# main.net
KiCad netlist of a schematic drawn in Altium Designer
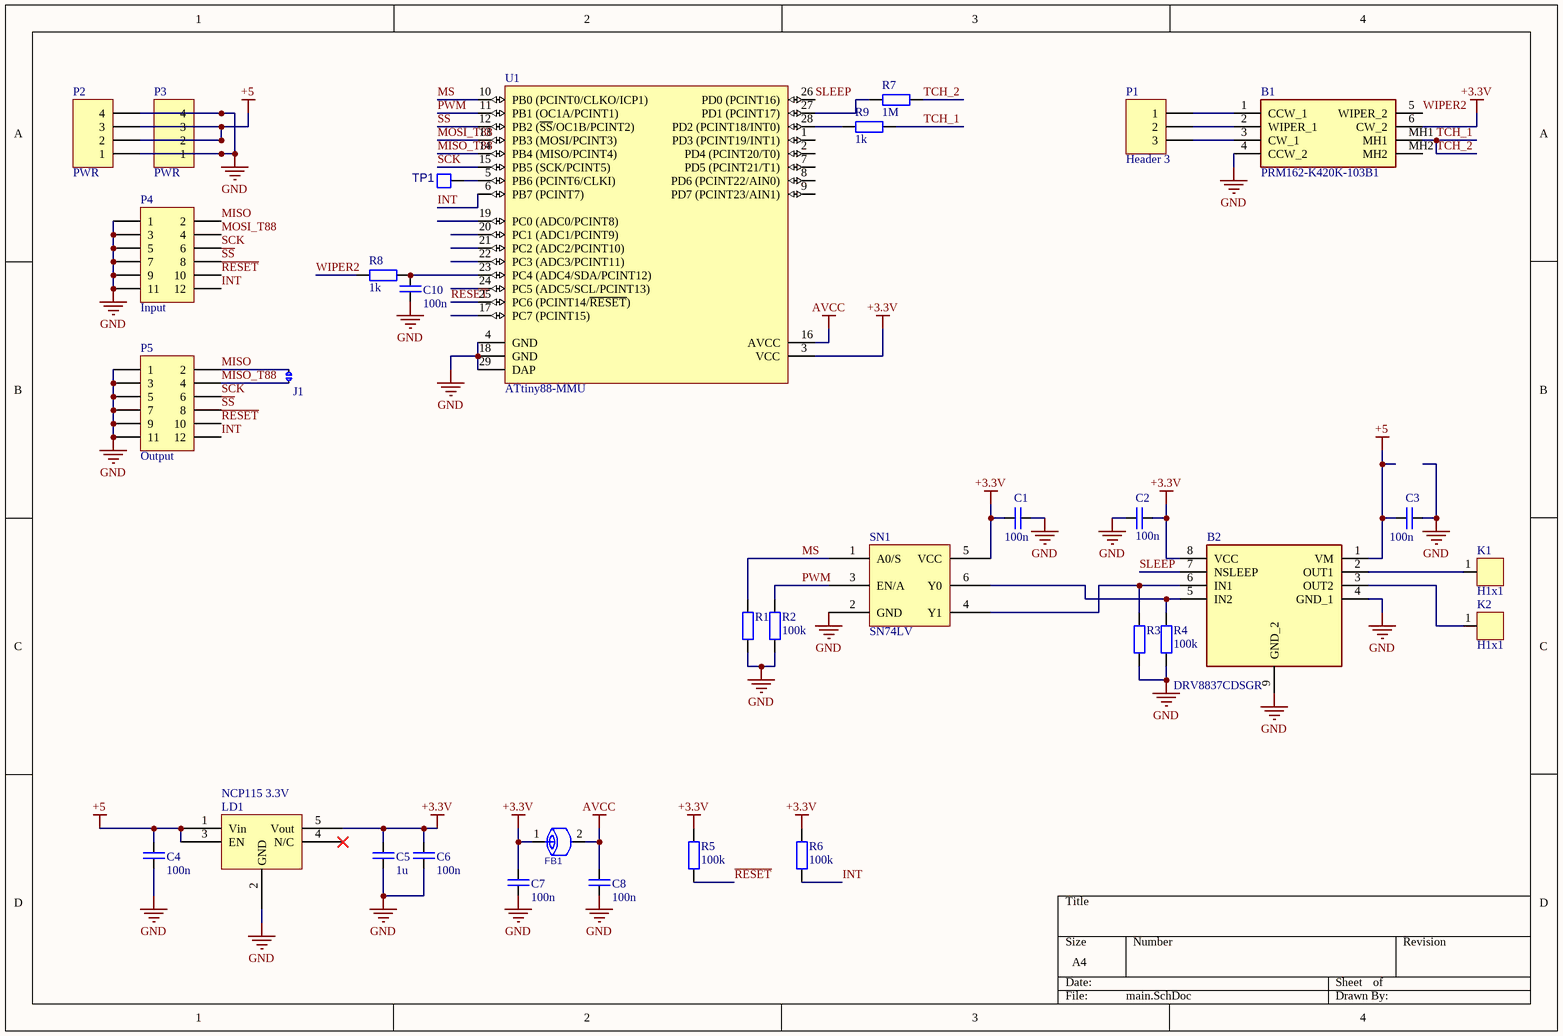
[diagram p0: main.SchDoc]

(export (version "E")
  (design (tool "Eeschema 10.0.6"))
  (components
    (comp (ref "B1")
      (value "PRM162-K420K-103B1")
      (footprint "PRM162K415K103B1")
      (description "Potentiometers 10KOHMS KNURLED DUAL NO DET")
      (fields (field (name "MOUSER PART NUMBER") "652-PRM162K420K103B1"))
      (libsource (lib "PRM162-K420K-103B1") (part "PRM162-K420K-103B1"))
    )
    (comp (ref "B2")
      (value "DRV8837CDSGR")
      (footprint "SON50P200X200X80-9N")
      (description "1A Low-Voltage H-Bridge Driver")
      (fields (field (name "MOUSER PART NUMBER") "595-DRV8837CDSGR"))
      (libsource (lib "DRV8837CDSGR") (part "DRV8837CDSGR"))
    )
    (comp (ref "C1")
      (value "100n")
      (footprint "R1005_0402i_M")
      (description "Capacitor")
      (libsource (lib "General") (part "C"))
    )
    (comp (ref "C2")
      (value "100n")
      (footprint "R1005_0402i_M")
      (description "Capacitor")
      (libsource (lib "General") (part "C"))
    )
    (comp (ref "C3")
      (value "100n")
      (footprint "R1005_0402i_M")
      (description "Capacitor")
      (libsource (lib "General") (part "C"))
    )
    (comp (ref "C4")
      (value "100n")
      (footprint "R1005_0402i_L")
      (description "Capacitor")
      (libsource (lib "General") (part "C"))
    )
    (comp (ref "C5")
      (value "1u")
      (footprint "C1608_0603I_L")
      (description "Capacitor")
      (libsource (lib "General") (part "C"))
    )
    (comp (ref "C6")
      (value "100n")
      (footprint "R1005_0402i_L")
      (description "Capacitor")
      (libsource (lib "General") (part "C"))
    )
    (comp (ref "C7")
      (value "100n")
      (footprint "R1005_0402i_L")
      (description "Capacitor")
      (libsource (lib "General") (part "C"))
    )
    (comp (ref "C8")
      (value "100n")
      (footprint "R1005_0402i_L")
      (description "Capacitor")
      (libsource (lib "General") (part "C"))
    )
    (comp (ref "C10")
      (value "100n")
      (footprint "R1005_0402i_M")
      (description "Capacitor")
      (libsource (lib "General") (part "C"))
    )
    (comp (ref "FB1")
      (value "FERITTE BEAD")
      (footprint "R1608_0603I_L")
      (libsource (lib "General") (part "FERITTE BEAD"))
    )
    (comp (ref "J1")
      (value "Terminator")
      (footprint "solderJumper")
      (libsource (lib "Kon_Tipk") (part "JMP_mini"))
    )
    (comp (ref "K1")
      (value "H1x1")
      (footprint "H1x1")
      (description "Header 1x1 (male)")
      (libsource (lib "Kon_Tipk") (part "H1x1"))
    )
    (comp (ref "K2")
      (value "H1x1")
      (footprint "H1x1")
      (description "Header 1x1 (male)")
      (libsource (lib "Kon_Tipk") (part "H1x1"))
    )
    (comp (ref "LD1")
      (value "NCP115 3.3V")
      (footprint "TSOP95P280X110-6L")
      (libsource (lib "led_ring") (part "NCP115 3.3V"))
    )
    (comp (ref "P1")
      (value "Header 3")
      (footprint "HDR1X3")
      (description "Header, 3-Pin")
      (fields (field (name "PUBLISHER") "Altium Limited"))
      (libsource (lib "Miscellaneous Connectors") (part "Header 3"))
    )
    (comp (ref "P2")
      (value "PWR")
      (footprint "HDR1X4")
      (description "Header, 4-Pin")
      (fields (field (name "PUBLISHER") "Altium Limited"))
      (libsource (lib "Miscellaneous Connectors") (part "Header 4"))
    )
    (comp (ref "P3")
      (value "PWR")
      (footprint "HDR1X4")
      (description "Header, 4-Pin")
      (fields (field (name "PUBLISHER") "Altium Limited"))
      (libsource (lib "Miscellaneous Connectors") (part "Header 4"))
    )
    (comp (ref "P4")
      (value "Input")
      (footprint "1.27mm SMD conn")
      (description "Header, 6-Pin, Dual row")
      (fields (field (name "PUBLISHER") "Altium Limited"))
      (libsource (lib "Miscellaneous Connectors") (part "Header 6X2"))
    )
    (comp (ref "P5")
      (value "Output")
      (footprint "1.27mm SMD conn")
      (description "Header, 6-Pin, Dual row")
      (fields (field (name "PUBLISHER") "Altium Limited"))
      (libsource (lib "Miscellaneous Connectors") (part "Header 6X2"))
    )
    (comp (ref "R1")
      (value "100k")
      (footprint "R1005_0402i_L")
      (description "R")
      (libsource (lib "General") (part "R"))
    )
    (comp (ref "R2")
      (value "100k")
      (footprint "R1005_0402i_L")
      (description "R")
      (libsource (lib "General") (part "R"))
    )
    (comp (ref "R3")
      (value "100k")
      (footprint "R1005_0402i_L")
      (description "R")
      (libsource (lib "General") (part "R"))
    )
    (comp (ref "R4")
      (value "100k")
      (footprint "R1005_0402i_L")
      (description "R")
      (libsource (lib "General") (part "R"))
    )
    (comp (ref "R5")
      (value "100k")
      (footprint "R1005_0402i_L")
      (description "R")
      (libsource (lib "General") (part "R"))
    )
    (comp (ref "R6")
      (value "100k")
      (footprint "R1005_0402i_L")
      (description "R")
      (libsource (lib "General") (part "R"))
    )
    (comp (ref "R7")
      (value "1M")
      (footprint "R1005_0402i_L")
      (description "R")
      (libsource (lib "General") (part "R"))
    )
    (comp (ref "R8")
      (value "1k")
      (footprint "R1005_0402i_L")
      (description "R")
      (libsource (lib "General") (part "R"))
    )
    (comp (ref "R9")
      (value "1k")
      (footprint "R1005_0402i_L")
      (description "R")
      (libsource (lib "General") (part "R"))
    )
    (comp (ref "SN1")
      (value "SN74LV")
      (footprint "SON35P100X40-6N")
      (libsource (lib "SN74LVC1G18DSFR") (part "SN74LV"))
    )
    (comp (ref "TP1") (value "PAD") (footprint "PAD") (libsource (lib "General") (part "PAD")))
    (comp (ref "U1")
      (value "ATtiny88-MMU")
      (footprint "28M1_N")
      (fields (field (name "PUBLISHER") "Altium Limited"))
      (libsource (lib "Atmel Microcontroller 8-Bit tinyAVR") (part "ATtiny88-MMU"))
    )
  )
  (nets
    (net (code "1") (name "+3.3V") (class "Default")
      (node (ref "B1") (pin "6") (pinfunction "CW_2_6") (pintype "passive"))
      (node (ref "B2") (pin "8") (pinfunction "VCC_8") (pintype "passive"))
      (node (ref "C1") (pin "2") (pinfunction "2_2") (pintype "passive"))
      (node (ref "C2") (pin "2") (pinfunction "2_2") (pintype "passive"))
      (node (ref "C5") (pin "1") (pinfunction "1_1") (pintype "passive"))
      (node (ref "C6") (pin "1") (pinfunction "1_1") (pintype "passive"))
      (node (ref "C7") (pin "1") (pinfunction "1_1") (pintype "passive"))
      (node (ref "FB1") (pin "1") (pintype "passive"))
      (node (ref "LD1") (pin "5") (pinfunction "Vout_5") (pintype "passive"))
      (node (ref "R5") (pin "1") (pintype "passive"))
      (node (ref "R6") (pin "1") (pintype "passive"))
      (node (ref "SN1") (pin "5") (pinfunction "VCC_5") (pintype "passive"))
      (node (ref "U1") (pin "3") (pinfunction "VCC_3") (pintype "power_in"))
    )
    (net (code "2") (name "+5") (class "Default")
      (node (ref "B2") (pin "1") (pinfunction "VM_1") (pintype "passive"))
      (node (ref "C3") (pin "1") (pinfunction "1_1") (pintype "passive"))
      (node (ref "C4") (pin "1") (pinfunction "1_1") (pintype "passive"))
      (node (ref "LD1") (pin "1") (pinfunction "Vin_1") (pintype "passive"))
      (node (ref "LD1") (pin "3") (pinfunction "EN_3") (pintype "passive"))
      (node (ref "P2") (pin "2") (pinfunction "2_2") (pintype "passive"))
      (node (ref "P2") (pin "3") (pinfunction "3_3") (pintype "passive"))
      (node (ref "P3") (pin "2") (pinfunction "2_2") (pintype "passive"))
      (node (ref "P3") (pin "3") (pinfunction "3_3") (pintype "passive"))
    )
    (net (code "3") (name "/INT") (class "Default")
      (node (ref "P4") (pin "12") (pinfunction "12_12") (pintype "passive"))
      (node (ref "P5") (pin "12") (pinfunction "12_12") (pintype "passive"))
      (node (ref "R6") (pin "2") (pintype "passive"))
      (node (ref "U1") (pin "6") (pinfunction "PB7_(PCINT7)_6") (pintype "bidirectional"))
    )
    (net (code "4") (name "/MISO") (class "Default")
      (node (ref "J1") (pin "2") (pinfunction "2_2") (pintype "passive"))
      (node (ref "P4") (pin "2") (pinfunction "2_2") (pintype "passive"))
      (node (ref "P5") (pin "2") (pinfunction "2_2") (pintype "passive"))
    )
    (net (code "5") (name "/MISO_T88") (class "Default")
      (node (ref "J1") (pin "1") (pinfunction "1_1") (pintype "passive"))
      (node (ref "P5") (pin "4") (pinfunction "4_4") (pintype "passive"))
      (node (ref "U1") (pin "14") (pinfunction "PB4_(MISO/PCINT4)_14") (pintype "bidirectional"))
    )
    (net (code "6") (name "/MOSI_T88") (class "Default")
      (node (ref "P4") (pin "4") (pinfunction "4_4") (pintype "passive"))
      (node (ref "U1") (pin "13") (pinfunction "PB3_(MOSI/PCINT3)_13") (pintype "bidirectional"))
    )
    (net (code "7") (name "/MS") (class "Default")
      (node (ref "R1") (pin "1") (pintype "passive"))
      (node (ref "SN1") (pin "1") (pinfunction "A0/S_1") (pintype "passive"))
      (node (ref "U1") (pin "10") (pinfunction "PB0_(PCINT0/CLKO/ICP1)_10") (pintype "bidirectional"))
    )
    (net (code "8") (name "/PWM") (class "Default")
      (node (ref "R2") (pin "1") (pintype "passive"))
      (node (ref "SN1") (pin "3") (pinfunction "EN/A_3") (pintype "passive"))
      (node (ref "U1") (pin "11") (pinfunction "PB1_(OC1A/PCINT1)_11") (pintype "bidirectional"))
    )
    (net (code "9") (name "/SCK") (class "Default")
      (node (ref "P4") (pin "6") (pinfunction "6_6") (pintype "passive"))
      (node (ref "P5") (pin "6") (pinfunction "6_6") (pintype "passive"))
      (node (ref "U1") (pin "15") (pinfunction "PB5_(SCK/PCINT5)_15") (pintype "bidirectional"))
    )
    (net (code "10") (name "/SLEEP") (class "Default")
      (node (ref "B2") (pin "7") (pinfunction "NSLEEP_7") (pintype "passive"))
      (node (ref "U1") (pin "26") (pinfunction "PD0_(PCINT16)_26") (pintype "bidirectional"))
    )
    (net (code "11") (name "/TCH_1") (class "Default")
      (node (ref "B1") (pin "MH1") (pinfunction "MH1_MH1") (pintype "passive"))
      (node (ref "R7") (pin "2") (pintype "passive"))
      (node (ref "R9") (pin "2") (pintype "passive"))
    )
    (net (code "12") (name "/WIPER2") (class "Default")
      (node (ref "B1") (pin "5") (pinfunction "WIPER_2_5") (pintype "passive"))
      (node (ref "R8") (pin "1") (pintype "passive"))
    )
    (net (code "13") (name "/~{RESET}") (class "Default")
      (node (ref "P4") (pin "10") (pinfunction "10_10") (pintype "passive"))
      (node (ref "P5") (pin "10") (pinfunction "10_10") (pintype "passive"))
      (node (ref "R5") (pin "2") (pintype "passive"))
      (node (ref "U1") (pin "25") (pinfunction "PC6_(PCINT14/~{RESET})_25") (pintype "bidirectional"))
    )
    (net (code "14") (name "/~{SS}") (class "Default")
      (node (ref "P4") (pin "8") (pinfunction "8_8") (pintype "passive"))
      (node (ref "P5") (pin "8") (pinfunction "8_8") (pintype "passive"))
      (node (ref "U1") (pin "12") (pinfunction "PB2_(~{SS}/OC1B/PCINT2)_12") (pintype "bidirectional"))
    )
    (net (code "15") (name "AVCC") (class "Default")
      (node (ref "C8") (pin "1") (pinfunction "1_1") (pintype "passive"))
      (node (ref "FB1") (pin "2") (pintype "passive"))
      (node (ref "U1") (pin "16") (pinfunction "AVCC_16") (pintype "power_in"))
    )
    (net (code "16") (name "GND") (class "Default")
      (node (ref "B1") (pin "4") (pinfunction "CCW_2_4") (pintype "passive"))
      (node (ref "B2") (pin "4") (pinfunction "GND_1_4") (pintype "passive"))
      (node (ref "B2") (pin "9") (pinfunction "GND_2_9") (pintype "passive"))
      (node (ref "C1") (pin "1") (pinfunction "1_1") (pintype "passive"))
      (node (ref "C10") (pin "2") (pinfunction "2_2") (pintype "passive"))
      (node (ref "C2") (pin "1") (pinfunction "1_1") (pintype "passive"))
      (node (ref "C3") (pin "2") (pinfunction "2_2") (pintype "passive"))
      (node (ref "C4") (pin "2") (pinfunction "2_2") (pintype "passive"))
      (node (ref "C5") (pin "2") (pinfunction "2_2") (pintype "passive"))
      (node (ref "C6") (pin "2") (pinfunction "2_2") (pintype "passive"))
      (node (ref "C7") (pin "2") (pinfunction "2_2") (pintype "passive"))
      (node (ref "C8") (pin "2") (pinfunction "2_2") (pintype "passive"))
      (node (ref "LD1") (pin "2") (pinfunction "GND_2") (pintype "passive"))
      (node (ref "P2") (pin "1") (pinfunction "1_1") (pintype "passive"))
      (node (ref "P2") (pin "4") (pinfunction "4_4") (pintype "passive"))
      (node (ref "P3") (pin "1") (pinfunction "1_1") (pintype "passive"))
      (node (ref "P3") (pin "4") (pinfunction "4_4") (pintype "passive"))
      (node (ref "P4") (pin "1") (pinfunction "1_1") (pintype "passive"))
      (node (ref "P4") (pin "11") (pinfunction "11_11") (pintype "passive"))
      (node (ref "P4") (pin "3") (pinfunction "3_3") (pintype "passive"))
      (node (ref "P4") (pin "5") (pinfunction "5_5") (pintype "passive"))
      (node (ref "P4") (pin "7") (pinfunction "7_7") (pintype "passive"))
      (node (ref "P4") (pin "9") (pinfunction "9_9") (pintype "passive"))
      (node (ref "P5") (pin "1") (pinfunction "1_1") (pintype "passive"))
      (node (ref "P5") (pin "11") (pinfunction "11_11") (pintype "passive"))
      (node (ref "P5") (pin "3") (pinfunction "3_3") (pintype "passive"))
      (node (ref "P5") (pin "5") (pinfunction "5_5") (pintype "passive"))
      (node (ref "P5") (pin "7") (pinfunction "7_7") (pintype "passive"))
      (node (ref "P5") (pin "9") (pinfunction "9_9") (pintype "passive"))
      (node (ref "R1") (pin "2") (pintype "passive"))
      (node (ref "R2") (pin "2") (pintype "passive"))
      (node (ref "R3") (pin "2") (pintype "passive"))
      (node (ref "R4") (pin "2") (pintype "passive"))
      (node (ref "SN1") (pin "2") (pinfunction "GND_2") (pintype "passive"))
      (node (ref "U1") (pin "18") (pinfunction "GND_18") (pintype "power_in"))
      (node (ref "U1") (pin "29") (pinfunction "DAP_29") (pintype "passive"))
      (node (ref "U1") (pin "4") (pinfunction "GND_4") (pintype "power_in"))
    )
    (net (code "17") (name "Net-(B1-CCW_1)") (class "Default")
      (node (ref "B1") (pin "1") (pinfunction "CCW_1_1") (pintype "passive"))
      (node (ref "P1") (pin "1") (pinfunction "1_1") (pintype "passive"))
    )
    (net (code "18") (name "Net-(B1-CW_1)") (class "Default")
      (node (ref "B1") (pin "3") (pinfunction "CW_1_3") (pintype "passive"))
      (node (ref "P1") (pin "3") (pinfunction "3_3") (pintype "passive"))
    )
    (net (code "19") (name "Net-(B1-WIPER_1)") (class "Default")
      (node (ref "B1") (pin "2") (pinfunction "WIPER_1_2") (pintype "passive"))
      (node (ref "P1") (pin "2") (pinfunction "2_2") (pintype "passive"))
    )
    (net (code "20") (name "Net-(B2-IN1)") (class "Default")
      (node (ref "B2") (pin "6") (pinfunction "IN1_6") (pintype "passive"))
      (node (ref "R3") (pin "1") (pintype "passive"))
      (node (ref "SN1") (pin "4") (pinfunction "Y1_4") (pintype "passive"))
    )
    (net (code "21") (name "Net-(B2-IN2)") (class "Default")
      (node (ref "B2") (pin "5") (pinfunction "IN2_5") (pintype "passive"))
      (node (ref "R4") (pin "1") (pintype "passive"))
      (node (ref "SN1") (pin "6") (pinfunction "Y0_6") (pintype "passive"))
    )
    (net (code "22") (name "Net-(B2-OUT1)") (class "Default")
      (node (ref "B2") (pin "2") (pinfunction "OUT1_2") (pintype "passive"))
      (node (ref "K1") (pin "1") (pinfunction "1_1") (pintype "passive"))
    )
    (net (code "23") (name "Net-(B2-OUT2)") (class "Default")
      (node (ref "B2") (pin "3") (pinfunction "OUT2_3") (pintype "passive"))
      (node (ref "K2") (pin "1") (pinfunction "1_1") (pintype "passive"))
    )
    (net (code "24") (name "Net-(U1-PB6_(PCINT6{slash}CLKI))") (class "Default")
      (node (ref "TP1") (pin "1") (pinfunction "1_1") (pintype "passive"))
      (node (ref "U1") (pin "5") (pinfunction "PB6_(PCINT6/CLKI)_5") (pintype "bidirectional"))
    )
    (net (code "25") (name "Net-(U1-PC4_(ADC4{slash}SDA{slash}PCINT12))") (class "Default")
      (node (ref "C10") (pin "1") (pinfunction "1_1") (pintype "passive"))
      (node (ref "R8") (pin "2") (pintype "passive"))
      (node (ref "U1") (pin "23") (pinfunction "PC4_(ADC4/SDA/PCINT12)_23") (pintype "bidirectional"))
    )
    (net (code "26") (name "Net-(U1-PD1_(PCINT17))") (class "Default")
      (node (ref "R7") (pin "1") (pintype "passive"))
      (node (ref "U1") (pin "27") (pinfunction "PD1_(PCINT17)_27") (pintype "bidirectional"))
    )
    (net (code "27") (name "Net-(U1-PD2_(PCINT18{slash}INT0))") (class "Default")
      (node (ref "R9") (pin "1") (pintype "passive"))
      (node (ref "U1") (pin "28") (pinfunction "PD2_(PCINT18/INT0)_28") (pintype "bidirectional"))
    )
    (net (code "28") (name "unconnected-(B1-PadMH2)") (class "Default")
      (node (ref "B1") (pin "MH2") (pinfunction "MH2_MH2") (pintype "passive"))
    )
    (net (code "29") (name "unconnected-(LD1-N{slash}C-Pad4)") (class "Default")
      (node (ref "LD1") (pin "4") (pinfunction "N/C_4") (pintype "passive+no_connect"))
    )
    (net (code "30") (name "unconnected-(U1-PC0_(ADC0{slash}PCINT8)-Pad19)") (class "Default")
      (node (ref "U1") (pin "19") (pinfunction "PC0_(ADC0/PCINT8)_19") (pintype "bidirectional"))
    )
    (net (code "31") (name "unconnected-(U1-PC1_(ADC1{slash}PCINT9)-Pad20)") (class "Default")
      (node (ref "U1") (pin "20") (pinfunction "PC1_(ADC1/PCINT9)_20") (pintype "bidirectional"))
    )
    (net (code "32") (name "unconnected-(U1-PC2_(ADC2{slash}PCINT10)-Pad21)") (class "Default")
      (node (ref "U1") (pin "21") (pinfunction "PC2_(ADC2/PCINT10)_21") (pintype "bidirectional"))
    )
    (net (code "33") (name "unconnected-(U1-PC3_(ADC3{slash}PCINT11)-Pad22)") (class "Default")
      (node (ref "U1") (pin "22") (pinfunction "PC3_(ADC3/PCINT11)_22") (pintype "bidirectional"))
    )
    (net (code "34") (name "unconnected-(U1-PC5_(ADC5{slash}SCL{slash}PCINT13)-Pad24)") (class "Default")
      (node (ref "U1") (pin "24") (pinfunction "PC5_(ADC5/SCL/PCINT13)_24") (pintype "bidirectional"))
    )
    (net (code "35") (name "unconnected-(U1-PC7_(PCINT15)-Pad17)") (class "Default")
      (node (ref "U1") (pin "17") (pinfunction "PC7_(PCINT15)_17") (pintype "bidirectional"))
    )
    (net (code "36") (name "unconnected-(U1-PD3_(PCINT19{slash}INT1)-Pad1)") (class "Default")
      (node (ref "U1") (pin "1") (pinfunction "PD3_(PCINT19/INT1)_1") (pintype "bidirectional"))
    )
    (net (code "37") (name "unconnected-(U1-PD4_(PCINT20{slash}T0)-Pad2)") (class "Default")
      (node (ref "U1") (pin "2") (pinfunction "PD4_(PCINT20/T0)_2") (pintype "bidirectional"))
    )
    (net (code "38") (name "unconnected-(U1-PD5_(PCINT21{slash}T1)-Pad7)") (class "Default")
      (node (ref "U1") (pin "7") (pinfunction "PD5_(PCINT21/T1)_7") (pintype "bidirectional"))
    )
    (net (code "39") (name "unconnected-(U1-PD6_(PCINT22{slash}AIN0)-Pad8)") (class "Default")
      (node (ref "U1") (pin "8") (pinfunction "PD6_(PCINT22/AIN0)_8") (pintype "bidirectional"))
    )
    (net (code "40") (name "unconnected-(U1-PD7_(PCINT23{slash}AIN1)-Pad9)") (class "Default")
      (node (ref "U1") (pin "9") (pinfunction "PD7_(PCINT23/AIN1)_9") (pintype "bidirectional"))
    )
  )
)
